# DAC_AFE.net
KiCad netlist of a schematic drawn in Altium Designer
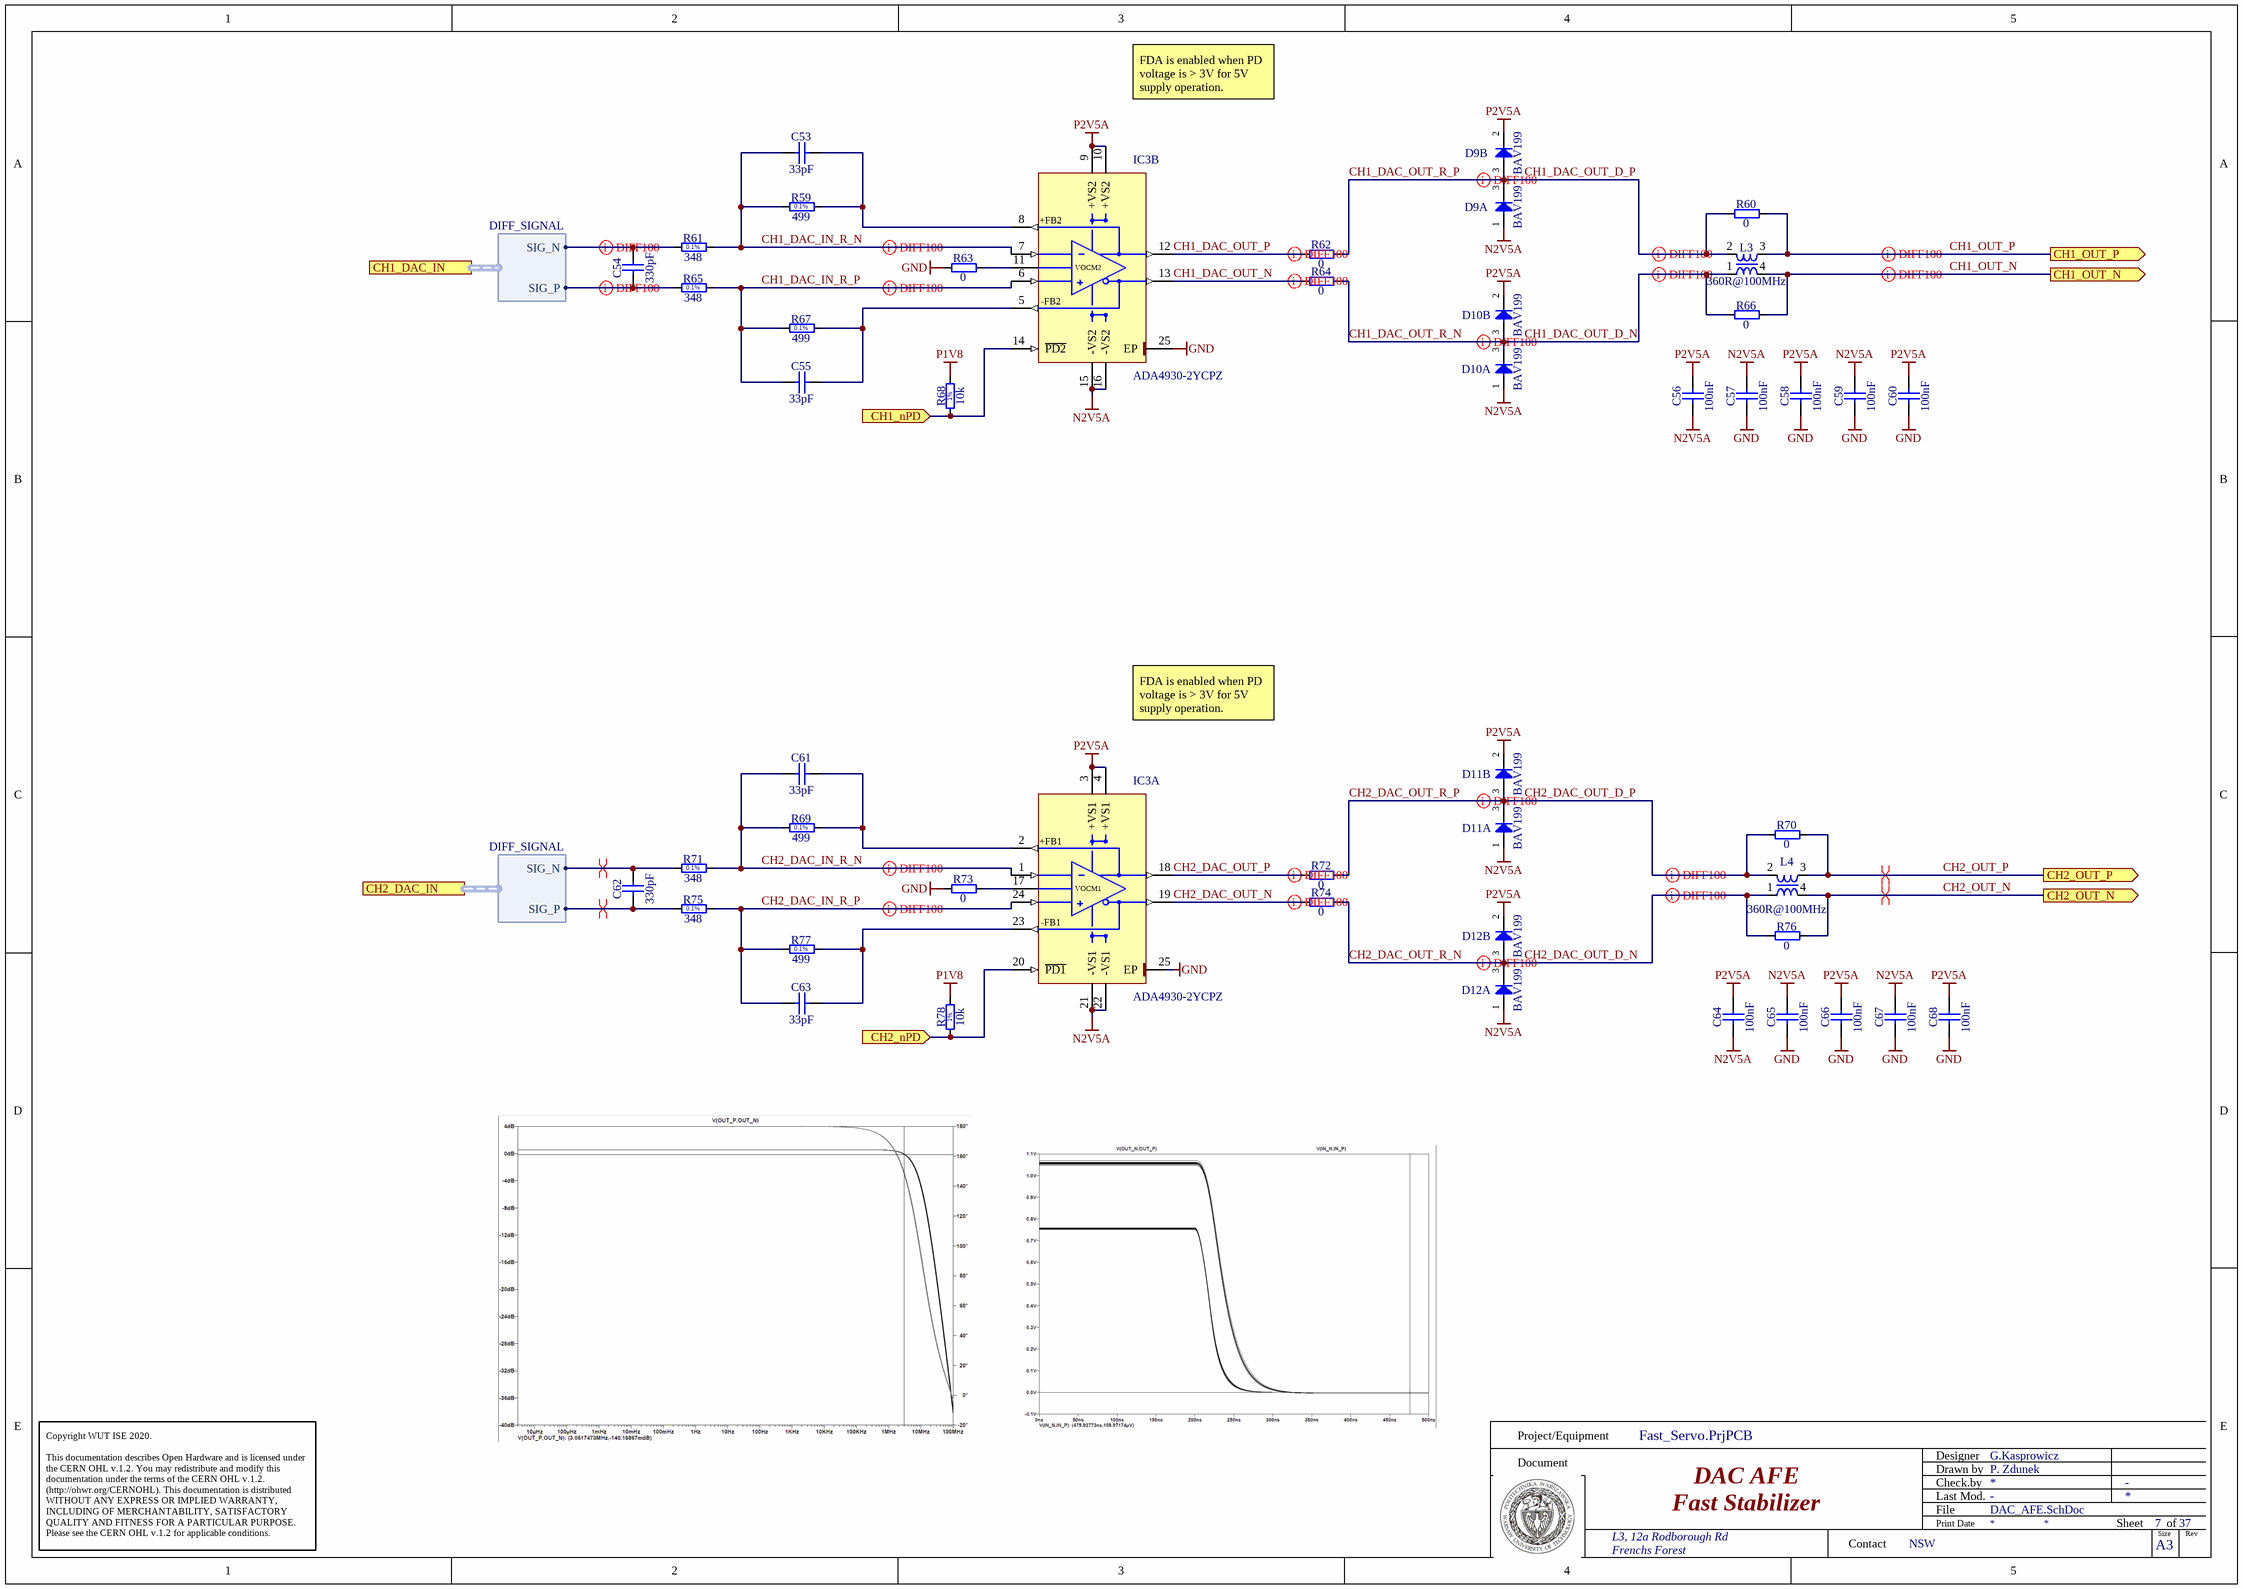
[diagram p0: DAC_AFE.SchDoc]

(export (version "E")
  (design (tool "Eeschema 10.0.6"))
  (components
    (comp (ref "C53")
      (value "33pF")
      (footprint "CAPC1608X87N")
      (description "Non-polarised capacitor")
      (fields
        (field (name "PART NUMBER") "CC0603_33PF_50V_5%_NP0")
        (field (name "VOLTAGE") "50V")
        (field (name "AUTHOR") "CERN DEM JLC")
      )
      (libsource (lib "Capacitors") (part "Capacitor - non polarized"))
    )
    (comp (ref "C54")
      (value "330pF")
      (footprint "CAPC1608X87N")
      (description "Non-polarised capacitor")
      (fields
        (field (name "PART NUMBER") "CC0603_330PF_50V_1%_NP0")
        (field (name "VOLTAGE") "50V")
        (field (name "AUTHOR") "CERN DEM MR")
      )
      (libsource (lib "Capacitors") (part "Capacitor - non polarized"))
    )
    (comp (ref "C55")
      (value "33pF")
      (footprint "CAPC1608X87N")
      (description "Non-polarised capacitor")
      (fields
        (field (name "PART NUMBER") "CC0603_33PF_50V_5%_NP0")
        (field (name "VOLTAGE") "50V")
        (field (name "AUTHOR") "CERN DEM JLC")
      )
      (libsource (lib "Capacitors") (part "Capacitor - non polarized"))
    )
    (comp (ref "C56")
      (value "100nF")
      (footprint "CAPC1005X55N")
      (description "Non-polarised capacitor")
      (fields
        (field (name "PART NUMBER") "CC0402_100NF_16V_10%_X7R")
        (field (name "VOLTAGE") "16V")
        (field (name "AUTHOR") "CERN DEM JLC")
      )
      (libsource (lib "Capacitors") (part "Capacitor - non polarized"))
    )
    (comp (ref "C57")
      (value "100nF")
      (footprint "CAPC1005X55N")
      (description "Non-polarised capacitor")
      (fields
        (field (name "PART NUMBER") "CC0402_100NF_16V_10%_X7R")
        (field (name "VOLTAGE") "16V")
        (field (name "AUTHOR") "CERN DEM JLC")
      )
      (libsource (lib "Capacitors") (part "Capacitor - non polarized"))
    )
    (comp (ref "C58")
      (value "100nF")
      (footprint "CAPC1005X55N")
      (description "Non-polarised capacitor")
      (fields
        (field (name "PART NUMBER") "CC0402_100NF_16V_10%_X7R")
        (field (name "VOLTAGE") "16V")
        (field (name "AUTHOR") "CERN DEM JLC")
      )
      (libsource (lib "Capacitors") (part "Capacitor - non polarized"))
    )
    (comp (ref "C59")
      (value "100nF")
      (footprint "CAPC1005X55N")
      (description "Non-polarised capacitor")
      (fields
        (field (name "PART NUMBER") "CC0402_100NF_16V_10%_X7R")
        (field (name "VOLTAGE") "16V")
        (field (name "AUTHOR") "CERN DEM JLC")
      )
      (libsource (lib "Capacitors") (part "Capacitor - non polarized"))
    )
    (comp (ref "C60")
      (value "100nF")
      (footprint "CAPC1005X55N")
      (description "Non-polarised capacitor")
      (fields
        (field (name "PART NUMBER") "CC0402_100NF_16V_10%_X7R")
        (field (name "VOLTAGE") "16V")
        (field (name "AUTHOR") "CERN DEM JLC")
      )
      (libsource (lib "Capacitors") (part "Capacitor - non polarized"))
    )
    (comp (ref "C61")
      (value "33pF")
      (footprint "CAPC1608X87N")
      (description "Non-polarised capacitor")
      (fields
        (field (name "PART NUMBER") "CC0603_33PF_50V_5%_NP0")
        (field (name "VOLTAGE") "50V")
        (field (name "AUTHOR") "CERN DEM JLC")
      )
      (libsource (lib "Capacitors") (part "Capacitor - non polarized"))
    )
    (comp (ref "C62")
      (value "330pF")
      (footprint "CAPC1608X87N")
      (description "Non-polarised capacitor")
      (fields
        (field (name "PART NUMBER") "CC0603_330PF_50V_1%_NP0")
        (field (name "VOLTAGE") "50V")
        (field (name "AUTHOR") "CERN DEM MR")
      )
      (libsource (lib "Capacitors") (part "Capacitor - non polarized"))
    )
    (comp (ref "C63")
      (value "33pF")
      (footprint "CAPC1608X87N")
      (description "Non-polarised capacitor")
      (fields
        (field (name "PART NUMBER") "CC0603_33PF_50V_5%_NP0")
        (field (name "VOLTAGE") "50V")
        (field (name "AUTHOR") "CERN DEM JLC")
      )
      (libsource (lib "Capacitors") (part "Capacitor - non polarized"))
    )
    (comp (ref "C64")
      (value "100nF")
      (footprint "CAPC1005X55N")
      (description "Non-polarised capacitor")
      (fields
        (field (name "PART NUMBER") "CC0402_100NF_16V_10%_X7R")
        (field (name "VOLTAGE") "16V")
        (field (name "AUTHOR") "CERN DEM JLC")
      )
      (libsource (lib "Capacitors") (part "Capacitor - non polarized"))
    )
    (comp (ref "C65")
      (value "100nF")
      (footprint "CAPC1005X55N")
      (description "Non-polarised capacitor")
      (fields
        (field (name "PART NUMBER") "CC0402_100NF_16V_10%_X7R")
        (field (name "VOLTAGE") "16V")
        (field (name "AUTHOR") "CERN DEM JLC")
      )
      (libsource (lib "Capacitors") (part "Capacitor - non polarized"))
    )
    (comp (ref "C66")
      (value "100nF")
      (footprint "CAPC1005X55N")
      (description "Non-polarised capacitor")
      (fields
        (field (name "PART NUMBER") "CC0402_100NF_16V_10%_X7R")
        (field (name "VOLTAGE") "16V")
        (field (name "AUTHOR") "CERN DEM JLC")
      )
      (libsource (lib "Capacitors") (part "Capacitor - non polarized"))
    )
    (comp (ref "C67")
      (value "100nF")
      (footprint "CAPC1005X55N")
      (description "Non-polarised capacitor")
      (fields
        (field (name "PART NUMBER") "CC0402_100NF_16V_10%_X7R")
        (field (name "VOLTAGE") "16V")
        (field (name "AUTHOR") "CERN DEM JLC")
      )
      (libsource (lib "Capacitors") (part "Capacitor - non polarized"))
    )
    (comp (ref "C68")
      (value "100nF")
      (footprint "CAPC1005X55N")
      (description "Non-polarised capacitor")
      (fields
        (field (name "PART NUMBER") "CC0402_100NF_16V_10%_X7R")
        (field (name "VOLTAGE") "16V")
        (field (name "AUTHOR") "CERN DEM JLC")
      )
      (libsource (lib "Capacitors") (part "Capacitor - non polarized"))
    )
    (comp (ref "D9")
      (value "BAV199")
      (footprint "SOT95P240X110-3N")
      (description "Serial Diode")
      (fields
        (field (name "VOLTAGE") "75V")
        (field (name "POWER") "250mW")
        (field (name "AUTHOR") "CERN DEM JMW")
      )
      (libsource (lib "ICs And Semiconductors") (part "Diode x2 A1C3_A3C2"))
    )
    (comp (ref "D10")
      (value "BAV199")
      (footprint "SOT95P240X110-3N")
      (description "Serial Diode")
      (fields
        (field (name "VOLTAGE") "75V")
        (field (name "POWER") "250mW")
        (field (name "AUTHOR") "CERN DEM JMW")
      )
      (libsource (lib "ICs And Semiconductors") (part "Diode x2 A1C3_A3C2"))
    )
    (comp (ref "D11")
      (value "BAV199")
      (footprint "SOT95P240X110-3N")
      (description "Serial Diode")
      (fields
        (field (name "VOLTAGE") "75V")
        (field (name "POWER") "250mW")
        (field (name "AUTHOR") "CERN DEM JMW")
      )
      (libsource (lib "ICs And Semiconductors") (part "Diode x2 A1C3_A3C2"))
    )
    (comp (ref "D12")
      (value "BAV199")
      (footprint "SOT95P240X110-3N")
      (description "Serial Diode")
      (fields
        (field (name "VOLTAGE") "75V")
        (field (name "POWER") "250mW")
        (field (name "AUTHOR") "CERN DEM JMW")
      )
      (libsource (lib "ICs And Semiconductors") (part "Diode x2 A1C3_A3C2"))
    )
    (comp (ref "IC3")
      (value "ADA4930-2YCPZ")
      (footprint "QFN50P400X400X80-25N-S240")
      (description "Ultralow Noise Drivers For Low Voltage ADCs")
      (fields (field (name "MANUFACTURER") "ANALOG DEVICES") (field (name "AUTHOR") "CERN DEM MR"))
      (libsource (lib "ICs And Semiconductors") (part "ADA4930-2"))
    )
    (comp (ref "L3")
      (value "360R@100MHz")
      (footprint "IND_TDK_ACM2012")
      (description "Inductor Common Mode")
      (fields
        (field (name "PART NUMBER") "IND_TDK_ACM2012-361-2P")
        (field (name "POWER") "220mA")
        (field (name "AUTHOR") "CERN DEM BC")
      )
      (libsource (lib "Inductors & Transformers") (part "Inductor Common Mode 1-4 2-3"))
    )
    (comp (ref "L4")
      (value "360R@100MHz")
      (footprint "IND_TDK_ACM2012")
      (description "Inductor Common Mode")
      (fields
        (field (name "PART NUMBER") "IND_TDK_ACM2012-361-2P")
        (field (name "POWER") "220mA")
        (field (name "AUTHOR") "CERN DEM BC")
      )
      (libsource (lib "Inductors & Transformers") (part "Inductor Common Mode 1-4 2-3"))
    )
    (comp (ref "R59")
      (value "499")
      (footprint "RESC1608X55N")
      (description "Resistor - 0.1%")
      (fields
        (field (name "PART NUMBER") "R0603_499R_0.1%_0.063W_10PPM")
        (field (name "POWER") "0.063W")
        (field (name "AUTHOR") "CERN DEM JLC")
      )
      (libsource (lib "Resistors") (part "Resistor - 0.1%"))
    )
    (comp (ref "R60")
      (value "0")
      (footprint "RESC1005X40N")
      (description "Resistor")
      (fields
        (field (name "PART NUMBER") "R0402_0R_JUMPER")
        (field (name "MANUFACTURER") "GENERIC")
        (field (name "AUTHOR") "CERN DEM JLC")
      )
      (libsource (lib "Resistors") (part "Resistor"))
    )
    (comp (ref "R61")
      (value "348")
      (footprint "RESC1608X55N")
      (description "Resistor - 0.1%")
      (fields
        (field (name "PART NUMBER") "R0603_348R_0.1%_0.063W_10PPM")
        (field (name "POWER") "0.063W")
        (field (name "AUTHOR") "CERN DEM JLC")
      )
      (libsource (lib "Resistors") (part "Resistor - 0.1%"))
    )
    (comp (ref "R62")
      (value "0")
      (footprint "RESC1005X40N")
      (description "Resistor")
      (fields
        (field (name "PART NUMBER") "R0402_0R_JUMPER")
        (field (name "MANUFACTURER") "GENERIC")
        (field (name "AUTHOR") "CERN DEM JLC")
      )
      (libsource (lib "Resistors") (part "Resistor"))
    )
    (comp (ref "R63")
      (value "0")
      (footprint "RESC1005X40N")
      (description "Resistor")
      (fields
        (field (name "PART NUMBER") "R0402_0R_JUMPER")
        (field (name "MANUFACTURER") "GENERIC")
        (field (name "AUTHOR") "CERN DEM JLC")
      )
      (libsource (lib "Resistors") (part "Resistor"))
    )
    (comp (ref "R64")
      (value "0")
      (footprint "RESC1005X40N")
      (description "Resistor")
      (fields
        (field (name "PART NUMBER") "R0402_0R_JUMPER")
        (field (name "MANUFACTURER") "GENERIC")
        (field (name "AUTHOR") "CERN DEM JLC")
      )
      (libsource (lib "Resistors") (part "Resistor"))
    )
    (comp (ref "R65")
      (value "348")
      (footprint "RESC1608X55N")
      (description "Resistor - 0.1%")
      (fields
        (field (name "PART NUMBER") "R0603_348R_0.1%_0.063W_10PPM")
        (field (name "POWER") "0.063W")
        (field (name "AUTHOR") "CERN DEM JLC")
      )
      (libsource (lib "Resistors") (part "Resistor - 0.1%"))
    )
    (comp (ref "R66")
      (value "0")
      (footprint "RESC1005X40N")
      (description "Resistor")
      (fields
        (field (name "PART NUMBER") "R0402_0R_JUMPER")
        (field (name "MANUFACTURER") "GENERIC")
        (field (name "AUTHOR") "CERN DEM JLC")
      )
      (libsource (lib "Resistors") (part "Resistor"))
    )
    (comp (ref "R67")
      (value "499")
      (footprint "RESC1608X55N")
      (description "Resistor - 0.1%")
      (fields
        (field (name "PART NUMBER") "R0603_499R_0.1%_0.063W_10PPM")
        (field (name "POWER") "0.063W")
        (field (name "AUTHOR") "CERN DEM JLC")
      )
      (libsource (lib "Resistors") (part "Resistor - 0.1%"))
    )
    (comp (ref "R68")
      (value "10k")
      (footprint "RESC1005X40N")
      (description "Resistor - 1%")
      (fields
        (field (name "PART NUMBER") "R0402_10K_1%_0.0625W_100PPM")
        (field (name "MANUFACTURER") "GENERIC")
        (field (name "AUTHOR") "CERN DEM JLC")
      )
      (libsource (lib "Resistors") (part "Resistor - 1%"))
    )
    (comp (ref "R69")
      (value "499")
      (footprint "RESC1608X55N")
      (description "Resistor - 0.1%")
      (fields
        (field (name "PART NUMBER") "R0603_499R_0.1%_0.063W_10PPM")
        (field (name "POWER") "0.063W")
        (field (name "AUTHOR") "CERN DEM JLC")
      )
      (libsource (lib "Resistors") (part "Resistor - 0.1%"))
    )
    (comp (ref "R70")
      (value "0")
      (footprint "RESC1005X40N")
      (description "Resistor")
      (fields
        (field (name "PART NUMBER") "R0402_0R_JUMPER")
        (field (name "MANUFACTURER") "GENERIC")
        (field (name "AUTHOR") "CERN DEM JLC")
      )
      (libsource (lib "Resistors") (part "Resistor"))
    )
    (comp (ref "R71")
      (value "348")
      (footprint "RESC1608X55N")
      (description "Resistor - 0.1%")
      (fields
        (field (name "PART NUMBER") "R0603_348R_0.1%_0.063W_10PPM")
        (field (name "POWER") "0.063W")
        (field (name "AUTHOR") "CERN DEM JLC")
      )
      (libsource (lib "Resistors") (part "Resistor - 0.1%"))
    )
    (comp (ref "R72")
      (value "0")
      (footprint "RESC1005X40N")
      (description "Resistor")
      (fields
        (field (name "PART NUMBER") "R0402_0R_JUMPER")
        (field (name "MANUFACTURER") "GENERIC")
        (field (name "AUTHOR") "CERN DEM JLC")
      )
      (libsource (lib "Resistors") (part "Resistor"))
    )
    (comp (ref "R73")
      (value "0")
      (footprint "RESC1005X40N")
      (description "Resistor")
      (fields
        (field (name "PART NUMBER") "R0402_0R_JUMPER")
        (field (name "MANUFACTURER") "GENERIC")
        (field (name "AUTHOR") "CERN DEM JLC")
      )
      (libsource (lib "Resistors") (part "Resistor"))
    )
    (comp (ref "R74")
      (value "0")
      (footprint "RESC1005X40N")
      (description "Resistor")
      (fields
        (field (name "PART NUMBER") "R0402_0R_JUMPER")
        (field (name "MANUFACTURER") "GENERIC")
        (field (name "AUTHOR") "CERN DEM JLC")
      )
      (libsource (lib "Resistors") (part "Resistor"))
    )
    (comp (ref "R75")
      (value "348")
      (footprint "RESC1608X55N")
      (description "Resistor - 0.1%")
      (fields
        (field (name "PART NUMBER") "R0603_348R_0.1%_0.063W_10PPM")
        (field (name "POWER") "0.063W")
        (field (name "AUTHOR") "CERN DEM JLC")
      )
      (libsource (lib "Resistors") (part "Resistor - 0.1%"))
    )
    (comp (ref "R76")
      (value "0")
      (footprint "RESC1005X40N")
      (description "Resistor")
      (fields
        (field (name "PART NUMBER") "R0402_0R_JUMPER")
        (field (name "MANUFACTURER") "GENERIC")
        (field (name "AUTHOR") "CERN DEM JLC")
      )
      (libsource (lib "Resistors") (part "Resistor"))
    )
    (comp (ref "R77")
      (value "499")
      (footprint "RESC1608X55N")
      (description "Resistor - 0.1%")
      (fields
        (field (name "PART NUMBER") "R0603_499R_0.1%_0.063W_10PPM")
        (field (name "POWER") "0.063W")
        (field (name "AUTHOR") "CERN DEM JLC")
      )
      (libsource (lib "Resistors") (part "Resistor - 0.1%"))
    )
    (comp (ref "R78")
      (value "10k")
      (footprint "RESC1005X40N")
      (description "Resistor - 1%")
      (fields
        (field (name "PART NUMBER") "R0402_10K_1%_0.0625W_100PPM")
        (field (name "MANUFACTURER") "GENERIC")
        (field (name "AUTHOR") "CERN DEM JLC")
      )
      (libsource (lib "Resistors") (part "Resistor - 1%"))
    )
  )
  (nets
    (net (code "2") (name "/CH1_DAC_IN_R_N") (class "Default")
      (node (ref "C53") (pin "1") (pinfunction "1_1") (pintype "passive"))
      (node (ref "IC3") (pin "7") (pinfunction "-IN2_7") (pintype "input"))
      (node (ref "R59") (pin "1") (pinfunction "1_1") (pintype "passive"))
      (node (ref "R61") (pin "2") (pinfunction "2_2") (pintype "passive"))
    )
    (net (code "3") (name "/CH1_DAC_IN_R_P") (class "Default")
      (node (ref "C55") (pin "1") (pinfunction "1_1") (pintype "passive"))
      (node (ref "IC3") (pin "6") (pinfunction "+IN2_6") (pintype "input"))
      (node (ref "R65") (pin "2") (pinfunction "2_2") (pintype "passive"))
      (node (ref "R67") (pin "1") (pinfunction "1_1") (pintype "passive"))
    )
    (net (code "4") (name "/CH1_DAC_OUT_D_N") (class "Default")
      (node (ref "D10") (pin "3") (pinfunction "COMAC_3") (pintype "passive"))
      (node (ref "L3") (pin "1") (pinfunction "1_1") (pintype "passive"))
      (node (ref "R64") (pin "2") (pinfunction "2_2") (pintype "passive"))
      (node (ref "R66") (pin "1") (pinfunction "1_1") (pintype "passive"))
    )
    (net (code "5") (name "/CH1_DAC_OUT_D_P") (class "Default")
      (node (ref "D9") (pin "3") (pinfunction "COMAC_3") (pintype "passive"))
      (node (ref "L3") (pin "2") (pinfunction "2_2") (pintype "passive"))
      (node (ref "R60") (pin "1") (pinfunction "1_1") (pintype "passive"))
      (node (ref "R62") (pin "2") (pinfunction "2_2") (pintype "passive"))
    )
    (net (code "6") (name "/CH1_DAC_OUT_N") (class "Default")
      (node (ref "IC3") (pin "13") (pinfunction "-OUT2_13") (pintype "output"))
      (node (ref "R64") (pin "1") (pinfunction "1_1") (pintype "passive"))
    )
    (net (code "7") (name "/CH1_DAC_OUT_P") (class "Default")
      (node (ref "IC3") (pin "12") (pinfunction "+OUT2_12") (pintype "output"))
      (node (ref "R62") (pin "1") (pinfunction "1_1") (pintype "passive"))
    )
    (net (code "8") (name "/CH1_OUT_N") (class "Default")
      (node (ref "L3") (pin "4") (pinfunction "4_4") (pintype "passive"))
      (node (ref "R66") (pin "2") (pinfunction "2_2") (pintype "passive"))
    )
    (net (code "9") (name "/CH1_OUT_P") (class "Default")
      (node (ref "L3") (pin "3") (pinfunction "3_3") (pintype "passive"))
      (node (ref "R60") (pin "2") (pinfunction "2_2") (pintype "passive"))
    )
    (net (code "10") (name "/CH1_nPD") (class "Default")
      (node (ref "IC3") (pin "14") (pinfunction "~{PD2}_14") (pintype "input"))
      (node (ref "R68") (pin "1") (pinfunction "1_1") (pintype "passive"))
    )
    (net (code "11") (name "/CH2_DAC_IN_R_N") (class "Default")
      (node (ref "C61") (pin "1") (pinfunction "1_1") (pintype "passive"))
      (node (ref "IC3") (pin "1") (pinfunction "-IN1_1") (pintype "input"))
      (node (ref "R69") (pin "1") (pinfunction "1_1") (pintype "passive"))
      (node (ref "R71") (pin "2") (pinfunction "2_2") (pintype "passive"))
    )
    (net (code "12") (name "/CH2_DAC_IN_R_P") (class "Default")
      (node (ref "C63") (pin "1") (pinfunction "1_1") (pintype "passive"))
      (node (ref "IC3") (pin "24") (pinfunction "+IN1_24") (pintype "input"))
      (node (ref "R75") (pin "2") (pinfunction "2_2") (pintype "passive"))
      (node (ref "R77") (pin "1") (pinfunction "1_1") (pintype "passive"))
    )
    (net (code "13") (name "/CH2_DAC_OUT_D_N") (class "Default")
      (node (ref "D12") (pin "3") (pinfunction "COMAC_3") (pintype "passive"))
      (node (ref "L4") (pin "1") (pinfunction "1_1") (pintype "passive"))
      (node (ref "R74") (pin "2") (pinfunction "2_2") (pintype "passive"))
      (node (ref "R76") (pin "1") (pinfunction "1_1") (pintype "passive"))
    )
    (net (code "14") (name "/CH2_DAC_OUT_D_P") (class "Default")
      (node (ref "D11") (pin "3") (pinfunction "COMAC_3") (pintype "passive"))
      (node (ref "L4") (pin "2") (pinfunction "2_2") (pintype "passive"))
      (node (ref "R70") (pin "1") (pinfunction "1_1") (pintype "passive"))
      (node (ref "R72") (pin "2") (pinfunction "2_2") (pintype "passive"))
    )
    (net (code "15") (name "/CH2_DAC_OUT_N") (class "Default")
      (node (ref "IC3") (pin "19") (pinfunction "-OUT1_19") (pintype "output"))
      (node (ref "R74") (pin "1") (pinfunction "1_1") (pintype "passive"))
    )
    (net (code "16") (name "/CH2_DAC_OUT_P") (class "Default")
      (node (ref "IC3") (pin "18") (pinfunction "+OUT1_18") (pintype "output"))
      (node (ref "R72") (pin "1") (pinfunction "1_1") (pintype "passive"))
    )
    (net (code "17") (name "/CH2_OUT_N") (class "Default")
      (node (ref "L4") (pin "4") (pinfunction "4_4") (pintype "passive"))
      (node (ref "R76") (pin "2") (pinfunction "2_2") (pintype "passive"))
    )
    (net (code "18") (name "/CH2_OUT_P") (class "Default")
      (node (ref "L4") (pin "3") (pinfunction "3_3") (pintype "passive"))
      (node (ref "R70") (pin "2") (pinfunction "2_2") (pintype "passive"))
    )
    (net (code "19") (name "/CH2_nPD") (class "Default")
      (node (ref "IC3") (pin "20") (pinfunction "~{PD1}_20") (pintype "input"))
      (node (ref "R78") (pin "1") (pinfunction "1_1") (pintype "passive"))
    )
    (net (code "21") (name "GND") (class "Default")
      (node (ref "C57") (pin "1") (pinfunction "1_1") (pintype "passive"))
      (node (ref "C58") (pin "1") (pinfunction "1_1") (pintype "passive"))
      (node (ref "C59") (pin "1") (pinfunction "1_1") (pintype "passive"))
      (node (ref "C60") (pin "1") (pinfunction "1_1") (pintype "passive"))
      (node (ref "C65") (pin "1") (pinfunction "1_1") (pintype "passive"))
      (node (ref "C66") (pin "1") (pinfunction "1_1") (pintype "passive"))
      (node (ref "C67") (pin "1") (pinfunction "1_1") (pintype "passive"))
      (node (ref "C68") (pin "1") (pinfunction "1_1") (pintype "passive"))
      (node (ref "IC3") (pin "25") (pinfunction "EP_25") (pintype "power_in"))
      (node (ref "R63") (pin "1") (pinfunction "1_1") (pintype "passive"))
      (node (ref "R73") (pin "1") (pinfunction "1_1") (pintype "passive"))
    )
    (net (code "22") (name "N2V5A") (class "Default")
      (node (ref "C56") (pin "1") (pinfunction "1_1") (pintype "passive"))
      (node (ref "C57") (pin "2") (pinfunction "2_2") (pintype "passive"))
      (node (ref "C59") (pin "2") (pinfunction "2_2") (pintype "passive"))
      (node (ref "C64") (pin "1") (pinfunction "1_1") (pintype "passive"))
      (node (ref "C65") (pin "2") (pinfunction "2_2") (pintype "passive"))
      (node (ref "C67") (pin "2") (pinfunction "2_2") (pintype "passive"))
      (node (ref "D10") (pin "1") (pinfunction "A_1") (pintype "passive"))
      (node (ref "D11") (pin "1") (pinfunction "A_1") (pintype "passive"))
      (node (ref "D12") (pin "1") (pinfunction "A_1") (pintype "passive"))
      (node (ref "D9") (pin "1") (pinfunction "A_1") (pintype "passive"))
      (node (ref "IC3") (pin "15") (pinfunction "-VS2_15") (pintype "power_in"))
      (node (ref "IC3") (pin "16") (pinfunction "-VS2_16") (pintype "power_in"))
      (node (ref "IC3") (pin "21") (pinfunction "-VS1_21") (pintype "power_in"))
      (node (ref "IC3") (pin "22") (pinfunction "-VS1_22") (pintype "power_in"))
    )
    (net (code "23") (name "Net-(C54-Pad1)") (class "Default")
      (node (ref "C54") (pin "1") (pinfunction "1_1") (pintype "passive"))
      (node (ref "R65") (pin "1") (pinfunction "1_1") (pintype "passive"))
    )
    (net (code "24") (name "Net-(C54-Pad2)") (class "Default")
      (node (ref "C54") (pin "2") (pinfunction "2_2") (pintype "passive"))
      (node (ref "R61") (pin "1") (pinfunction "1_1") (pintype "passive"))
    )
    (net (code "25") (name "Net-(C62-Pad1)") (class "Default")
      (node (ref "C62") (pin "1") (pinfunction "1_1") (pintype "passive"))
      (node (ref "R75") (pin "1") (pinfunction "1_1") (pintype "passive"))
    )
    (net (code "26") (name "Net-(C62-Pad2)") (class "Default")
      (node (ref "C62") (pin "2") (pinfunction "2_2") (pintype "passive"))
      (node (ref "R71") (pin "1") (pinfunction "1_1") (pintype "passive"))
    )
    (net (code "27") (name "Net-(IC3A-+FB1)") (class "Default")
      (node (ref "C61") (pin "2") (pinfunction "2_2") (pintype "passive"))
      (node (ref "IC3") (pin "2") (pinfunction "+FB1_2") (pintype "output"))
      (node (ref "R69") (pin "2") (pinfunction "2_2") (pintype "passive"))
    )
    (net (code "28") (name "Net-(IC3A--FB1)") (class "Default")
      (node (ref "C63") (pin "2") (pinfunction "2_2") (pintype "passive"))
      (node (ref "IC3") (pin "23") (pinfunction "-FB1_23") (pintype "output"))
      (node (ref "R77") (pin "2") (pinfunction "2_2") (pintype "passive"))
    )
    (net (code "29") (name "Net-(IC3A-VOCM1)") (class "Default")
      (node (ref "IC3") (pin "17") (pinfunction "VOCM1_17") (pintype "passive"))
      (node (ref "R73") (pin "2") (pinfunction "2_2") (pintype "passive"))
    )
    (net (code "30") (name "Net-(IC3B-+FB2)") (class "Default")
      (node (ref "C53") (pin "2") (pinfunction "2_2") (pintype "passive"))
      (node (ref "IC3") (pin "8") (pinfunction "+FB2_8") (pintype "output"))
      (node (ref "R59") (pin "2") (pinfunction "2_2") (pintype "passive"))
    )
    (net (code "31") (name "Net-(IC3B--FB2)") (class "Default")
      (node (ref "C55") (pin "2") (pinfunction "2_2") (pintype "passive"))
      (node (ref "IC3") (pin "5") (pinfunction "-FB2_5") (pintype "output"))
      (node (ref "R67") (pin "2") (pinfunction "2_2") (pintype "passive"))
    )
    (net (code "32") (name "Net-(IC3B-VOCM2)") (class "Default")
      (node (ref "IC3") (pin "11") (pinfunction "VOCM2_11") (pintype "passive"))
      (node (ref "R63") (pin "2") (pinfunction "2_2") (pintype "passive"))
    )
    (net (code "33") (name "P1V8") (class "Default")
      (node (ref "R68") (pin "2") (pinfunction "2_2") (pintype "passive"))
      (node (ref "R78") (pin "2") (pinfunction "2_2") (pintype "passive"))
    )
    (net (code "34") (name "P2V5A") (class "Default")
      (node (ref "C56") (pin "2") (pinfunction "2_2") (pintype "passive"))
      (node (ref "C58") (pin "2") (pinfunction "2_2") (pintype "passive"))
      (node (ref "C60") (pin "2") (pinfunction "2_2") (pintype "passive"))
      (node (ref "C64") (pin "2") (pinfunction "2_2") (pintype "passive"))
      (node (ref "C66") (pin "2") (pinfunction "2_2") (pintype "passive"))
      (node (ref "C68") (pin "2") (pinfunction "2_2") (pintype "passive"))
      (node (ref "D10") (pin "2") (pinfunction "C_2") (pintype "passive"))
      (node (ref "D11") (pin "2") (pinfunction "C_2") (pintype "passive"))
      (node (ref "D12") (pin "2") (pinfunction "C_2") (pintype "passive"))
      (node (ref "D9") (pin "2") (pinfunction "C_2") (pintype "passive"))
      (node (ref "IC3") (pin "10") (pinfunction "+VS2_10") (pintype "power_in"))
      (node (ref "IC3") (pin "3") (pinfunction "+VS1_3") (pintype "power_in"))
      (node (ref "IC3") (pin "4") (pinfunction "+VS1_4") (pintype "power_in"))
      (node (ref "IC3") (pin "9") (pinfunction "+VS2_9") (pintype "power_in"))
    )
  )
)
